# e-Tapperhandpiece14.net
KiCad netlist of a schematic drawn in EAGLE
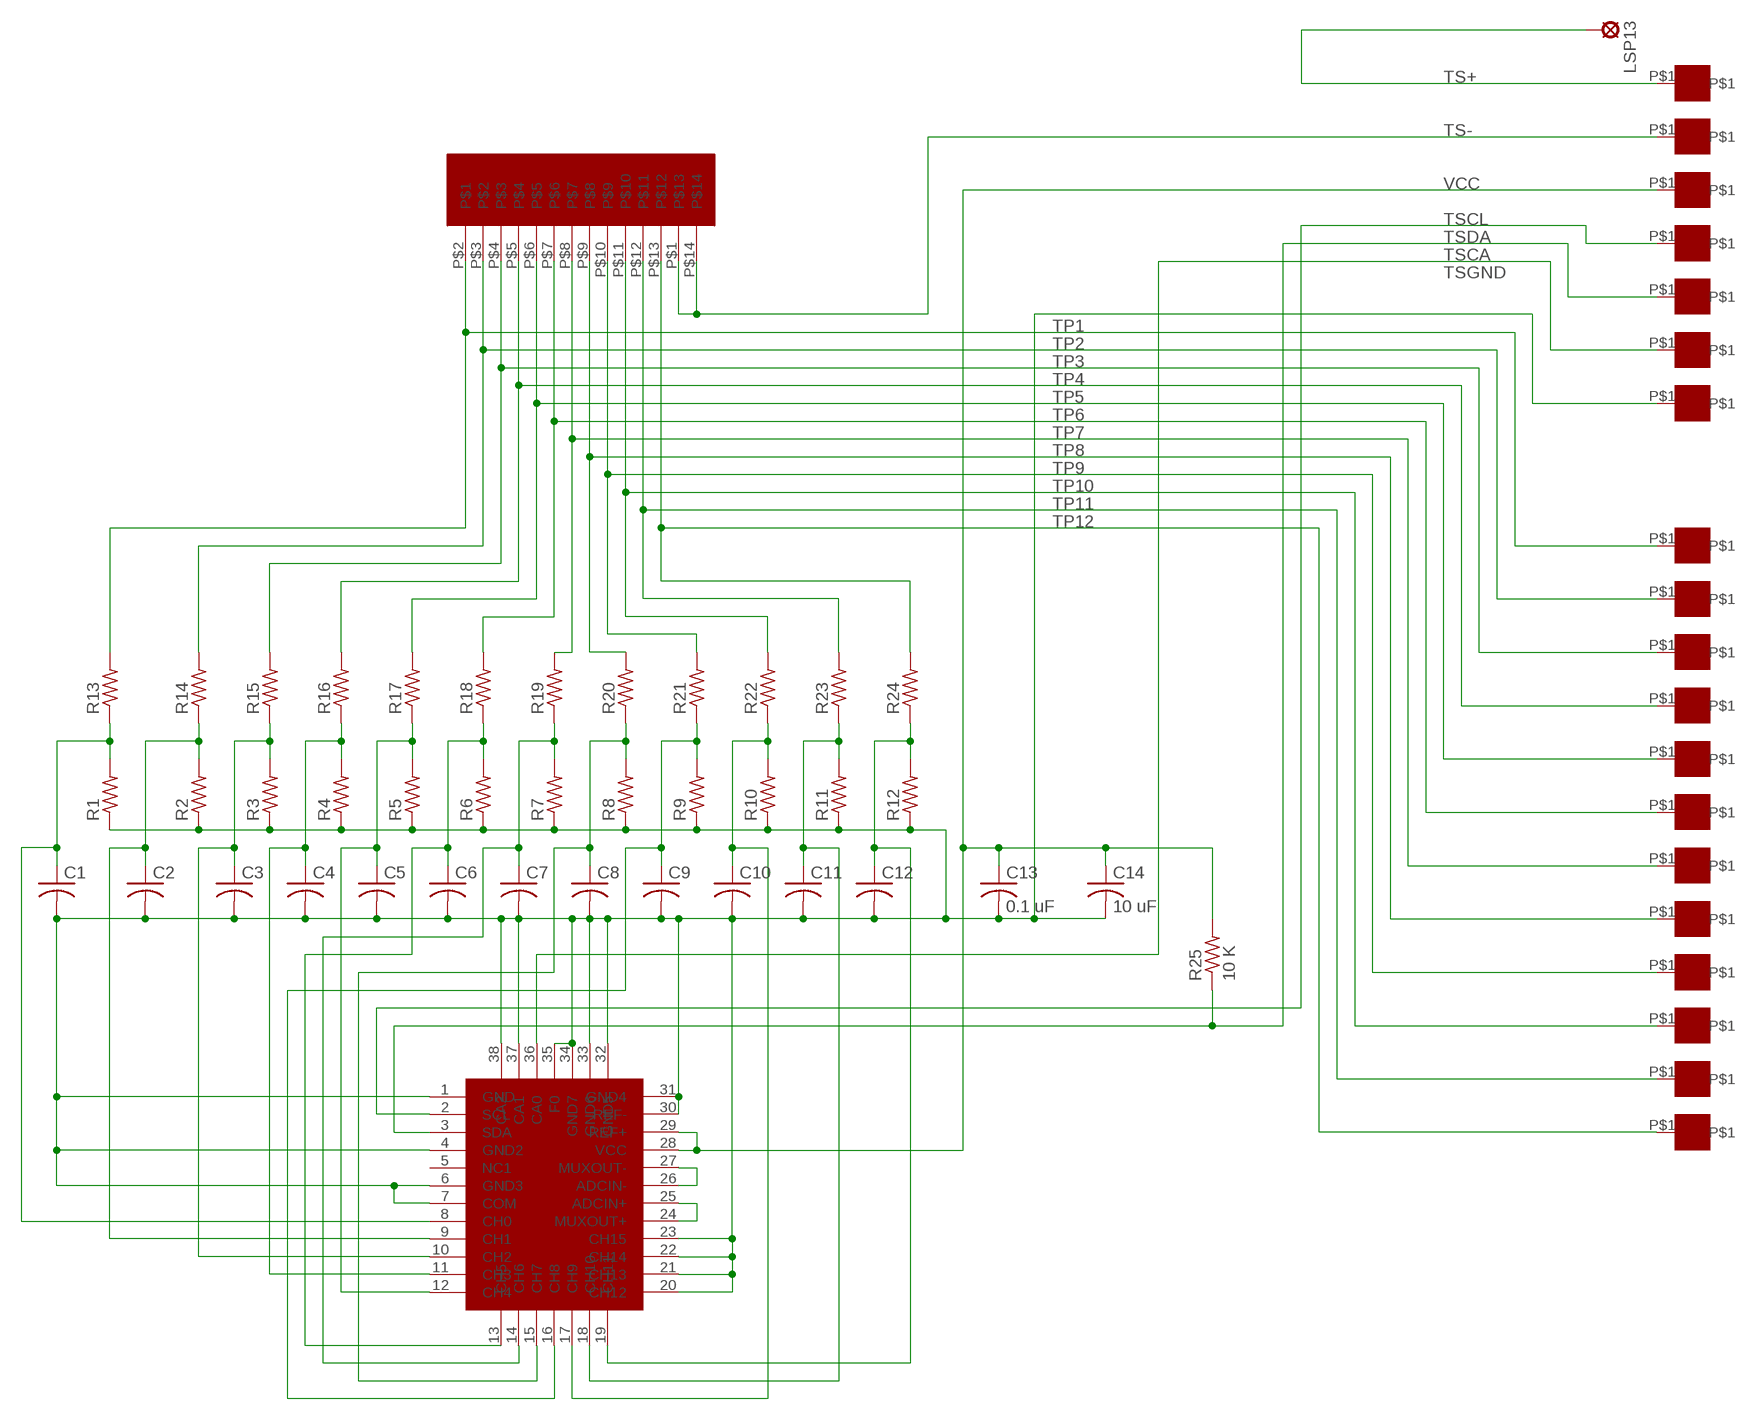
[diagram p0: schematic, sheet 1]

(export (version "E")
  (design (tool "Eeschema 10.0.6"))
  (components
    (comp (ref "C1")
      (value "C-USC0603")
      (footprint "eagle-import:C0603")
      (libsource (lib "eagle-import") (part "C-USC0603"))
    )
    (comp (ref "C2")
      (value "C-USC0603")
      (footprint "eagle-import:C0603")
      (libsource (lib "eagle-import") (part "C-USC0603"))
    )
    (comp (ref "C3")
      (value "C-USC0603")
      (footprint "eagle-import:C0603")
      (libsource (lib "eagle-import") (part "C-USC0603"))
    )
    (comp (ref "C4")
      (value "C-USC0603")
      (footprint "eagle-import:C0603")
      (libsource (lib "eagle-import") (part "C-USC0603"))
    )
    (comp (ref "C5")
      (value "C-USC0603")
      (footprint "eagle-import:C0603")
      (libsource (lib "eagle-import") (part "C-USC0603"))
    )
    (comp (ref "C6")
      (value "C-USC0603")
      (footprint "eagle-import:C0603")
      (libsource (lib "eagle-import") (part "C-USC0603"))
    )
    (comp (ref "C7")
      (value "C-USC0603")
      (footprint "eagle-import:C0603")
      (libsource (lib "eagle-import") (part "C-USC0603"))
    )
    (comp (ref "C8")
      (value "C-USC0603")
      (footprint "eagle-import:C0603")
      (libsource (lib "eagle-import") (part "C-USC0603"))
    )
    (comp (ref "C9")
      (value "C-USC0603")
      (footprint "eagle-import:C0603")
      (libsource (lib "eagle-import") (part "C-USC0603"))
    )
    (comp (ref "C10")
      (value "C-USC0603")
      (footprint "eagle-import:C0603")
      (libsource (lib "eagle-import") (part "C-USC0603"))
    )
    (comp (ref "C11")
      (value "C-USC0603")
      (footprint "eagle-import:C0603")
      (libsource (lib "eagle-import") (part "C-USC0603"))
    )
    (comp (ref "C12")
      (value "C-USC0603")
      (footprint "eagle-import:C0603")
      (libsource (lib "eagle-import") (part "C-USC0603"))
    )
    (comp (ref "C13")
      (value "0.1 uF")
      (footprint "eagle-import:C0603")
      (libsource (lib "eagle-import") (part "C-USC0603"))
    )
    (comp (ref "C14")
      (value "10 uF")
      (footprint "eagle-import:C0805")
      (libsource (lib "eagle-import") (part "C-USC0805"))
    )
    (comp (ref "LSP13")
      (value "SE11")
      (footprint "eagle-import:SE11")
      (libsource (lib "eagle-import") (part "SE11"))
    )
    (comp (ref "R1")
      (value "R-US_R0402")
      (footprint "eagle-import:R0402")
      (libsource (lib "eagle-import") (part "R-US_R0402"))
    )
    (comp (ref "R2")
      (value "R-US_R0402")
      (footprint "eagle-import:R0402")
      (libsource (lib "eagle-import") (part "R-US_R0402"))
    )
    (comp (ref "R3")
      (value "R-US_R0402")
      (footprint "eagle-import:R0402")
      (libsource (lib "eagle-import") (part "R-US_R0402"))
    )
    (comp (ref "R4")
      (value "R-US_R0402")
      (footprint "eagle-import:R0402")
      (libsource (lib "eagle-import") (part "R-US_R0402"))
    )
    (comp (ref "R5")
      (value "R-US_R0402")
      (footprint "eagle-import:R0402")
      (libsource (lib "eagle-import") (part "R-US_R0402"))
    )
    (comp (ref "R6")
      (value "R-US_R0402")
      (footprint "eagle-import:R0402")
      (libsource (lib "eagle-import") (part "R-US_R0402"))
    )
    (comp (ref "R7")
      (value "R-US_R0402")
      (footprint "eagle-import:R0402")
      (libsource (lib "eagle-import") (part "R-US_R0402"))
    )
    (comp (ref "R8")
      (value "R-US_R0402")
      (footprint "eagle-import:R0402")
      (libsource (lib "eagle-import") (part "R-US_R0402"))
    )
    (comp (ref "R9")
      (value "R-US_R0402")
      (footprint "eagle-import:R0402")
      (libsource (lib "eagle-import") (part "R-US_R0402"))
    )
    (comp (ref "R10")
      (value "R-US_R0402")
      (footprint "eagle-import:R0402")
      (libsource (lib "eagle-import") (part "R-US_R0402"))
    )
    (comp (ref "R11")
      (value "R-US_R0402")
      (footprint "eagle-import:R0402")
      (libsource (lib "eagle-import") (part "R-US_R0402"))
    )
    (comp (ref "R12")
      (value "R-US_R0402")
      (footprint "eagle-import:R0402")
      (libsource (lib "eagle-import") (part "R-US_R0402"))
    )
    (comp (ref "R13")
      (value "R-US_R0402")
      (footprint "eagle-import:R0402")
      (libsource (lib "eagle-import") (part "R-US_R0402"))
    )
    (comp (ref "R14")
      (value "R-US_R0402")
      (footprint "eagle-import:R0402")
      (libsource (lib "eagle-import") (part "R-US_R0402"))
    )
    (comp (ref "R15")
      (value "R-US_R0402")
      (footprint "eagle-import:R0402")
      (libsource (lib "eagle-import") (part "R-US_R0402"))
    )
    (comp (ref "R16")
      (value "R-US_R0402")
      (footprint "eagle-import:R0402")
      (libsource (lib "eagle-import") (part "R-US_R0402"))
    )
    (comp (ref "R17")
      (value "R-US_R0402")
      (footprint "eagle-import:R0402")
      (libsource (lib "eagle-import") (part "R-US_R0402"))
    )
    (comp (ref "R18")
      (value "R-US_R0402")
      (footprint "eagle-import:R0402")
      (libsource (lib "eagle-import") (part "R-US_R0402"))
    )
    (comp (ref "R19")
      (value "R-US_R0402")
      (footprint "eagle-import:R0402")
      (libsource (lib "eagle-import") (part "R-US_R0402"))
    )
    (comp (ref "R20")
      (value "R-US_R0402")
      (footprint "eagle-import:R0402")
      (libsource (lib "eagle-import") (part "R-US_R0402"))
    )
    (comp (ref "R21")
      (value "R-US_R0402")
      (footprint "eagle-import:R0402")
      (libsource (lib "eagle-import") (part "R-US_R0402"))
    )
    (comp (ref "R22")
      (value "R-US_R0402")
      (footprint "eagle-import:R0402")
      (libsource (lib "eagle-import") (part "R-US_R0402"))
    )
    (comp (ref "R23")
      (value "R-US_R0402")
      (footprint "eagle-import:R0402")
      (libsource (lib "eagle-import") (part "R-US_R0402"))
    )
    (comp (ref "R24")
      (value "R-US_R0402")
      (footprint "eagle-import:R0402")
      (libsource (lib "eagle-import") (part "R-US_R0402"))
    )
    (comp (ref "R25")
      (value "10 K")
      (footprint "eagle-import:R0402")
      (libsource (lib "eagle-import") (part "R-US_R0402"))
    )
    (comp (ref "TSP1")
      (value "ET1")
      (footprint "eagle-import:ET1")
      (libsource (lib "eagle-import") (part "ET1"))
    )
    (comp (ref "TSP2")
      (value "ET1")
      (footprint "eagle-import:ET1")
      (libsource (lib "eagle-import") (part "ET1"))
    )
    (comp (ref "TSP3")
      (value "ET1")
      (footprint "eagle-import:ET1")
      (libsource (lib "eagle-import") (part "ET1"))
    )
    (comp (ref "TSP4")
      (value "ET1")
      (footprint "eagle-import:ET1")
      (libsource (lib "eagle-import") (part "ET1"))
    )
    (comp (ref "TSP5")
      (value "ET1")
      (footprint "eagle-import:ET1")
      (libsource (lib "eagle-import") (part "ET1"))
    )
    (comp (ref "TSP6")
      (value "ET1")
      (footprint "eagle-import:ET1")
      (libsource (lib "eagle-import") (part "ET1"))
    )
    (comp (ref "TSP7")
      (value "ET1")
      (footprint "eagle-import:ET1")
      (libsource (lib "eagle-import") (part "ET1"))
    )
    (comp (ref "TSP8")
      (value "ET1")
      (footprint "eagle-import:ET1")
      (libsource (lib "eagle-import") (part "ET1"))
    )
    (comp (ref "TSP9")
      (value "ET1")
      (footprint "eagle-import:ET1")
      (libsource (lib "eagle-import") (part "ET1"))
    )
    (comp (ref "TSP10")
      (value "ET1")
      (footprint "eagle-import:ET1")
      (libsource (lib "eagle-import") (part "ET1"))
    )
    (comp (ref "TSP11")
      (value "ET1")
      (footprint "eagle-import:ET1")
      (libsource (lib "eagle-import") (part "ET1"))
    )
    (comp (ref "TSP12")
      (value "ET1")
      (footprint "eagle-import:ET1")
      (libsource (lib "eagle-import") (part "ET1"))
    )
    (comp (ref "TSP13")
      (value "ET1")
      (footprint "eagle-import:ET1")
      (libsource (lib "eagle-import") (part "ET1"))
    )
    (comp (ref "TSP14")
      (value "ET1")
      (footprint "eagle-import:ET1")
      (libsource (lib "eagle-import") (part "ET1"))
    )
    (comp (ref "TSP15")
      (value "ET1")
      (footprint "eagle-import:ET1")
      (libsource (lib "eagle-import") (part "ET1"))
    )
    (comp (ref "TSP16")
      (value "ET1")
      (footprint "eagle-import:ET1")
      (libsource (lib "eagle-import") (part "ET1"))
    )
    (comp (ref "TSP17")
      (value "ET1")
      (footprint "eagle-import:ET1")
      (libsource (lib "eagle-import") (part "ET1"))
    )
    (comp (ref "TSP18")
      (value "ET1")
      (footprint "eagle-import:ET1")
      (libsource (lib "eagle-import") (part "ET1"))
    )
    (comp (ref "TSP19")
      (value "ET1")
      (footprint "eagle-import:ET1")
      (libsource (lib "eagle-import") (part "ET1"))
    )
    (comp (ref "U$1")
      (value "LTC2497")
      (footprint "eagle-import:QFN38-5X7")
      (libsource (lib "eagle-import") (part "LTC2497"))
    )
    (comp (ref "U$2")
      (value "SS112D01")
      (footprint "eagle-import:SS112D01")
      (libsource (lib "eagle-import") (part "SS112D01"))
    )
  )
  (nets
    (net (code "1") (name "/TP1") (class "Default")
      (node (ref "R13") (pin "2") (pinfunction "2_2") (pintype "passive"))
      (node (ref "TSP1") (pin "P$1") (pinfunction "P$1_P$1") (pintype "bidirectional"))
      (node (ref "U$2") (pin "P$2") (pinfunction "P$1_P$2") (pintype "bidirectional"))
    )
    (net (code "2") (name "/TP2") (class "Default")
      (node (ref "R14") (pin "2") (pinfunction "2_2") (pintype "passive"))
      (node (ref "TSP2") (pin "P$1") (pinfunction "P$1_P$1") (pintype "bidirectional"))
      (node (ref "U$2") (pin "P$3") (pinfunction "P$2_P$3") (pintype "bidirectional"))
    )
    (net (code "3") (name "/TP3") (class "Default")
      (node (ref "R15") (pin "2") (pinfunction "2_2") (pintype "passive"))
      (node (ref "TSP3") (pin "P$1") (pinfunction "P$1_P$1") (pintype "bidirectional"))
      (node (ref "U$2") (pin "P$4") (pinfunction "P$3_P$4") (pintype "bidirectional"))
    )
    (net (code "4") (name "/TP4") (class "Default")
      (node (ref "R16") (pin "2") (pinfunction "2_2") (pintype "passive"))
      (node (ref "TSP4") (pin "P$1") (pinfunction "P$1_P$1") (pintype "bidirectional"))
      (node (ref "U$2") (pin "P$5") (pinfunction "P$4_P$5") (pintype "bidirectional"))
    )
    (net (code "5") (name "/TP5") (class "Default")
      (node (ref "R17") (pin "2") (pinfunction "2_2") (pintype "passive"))
      (node (ref "TSP5") (pin "P$1") (pinfunction "P$1_P$1") (pintype "bidirectional"))
      (node (ref "U$2") (pin "P$6") (pinfunction "P$5_P$6") (pintype "bidirectional"))
    )
    (net (code "6") (name "/TP6") (class "Default")
      (node (ref "R18") (pin "2") (pinfunction "2_2") (pintype "passive"))
      (node (ref "TSP6") (pin "P$1") (pinfunction "P$1_P$1") (pintype "bidirectional"))
      (node (ref "U$2") (pin "P$7") (pinfunction "P$6_P$7") (pintype "bidirectional"))
    )
    (net (code "7") (name "/TP7") (class "Default")
      (node (ref "R19") (pin "2") (pinfunction "2_2") (pintype "passive"))
      (node (ref "TSP7") (pin "P$1") (pinfunction "P$1_P$1") (pintype "bidirectional"))
      (node (ref "U$2") (pin "P$8") (pinfunction "P$7_P$8") (pintype "bidirectional"))
    )
    (net (code "8") (name "/TP8") (class "Default")
      (node (ref "R20") (pin "2") (pinfunction "2_2") (pintype "passive"))
      (node (ref "TSP8") (pin "P$1") (pinfunction "P$1_P$1") (pintype "bidirectional"))
      (node (ref "U$2") (pin "P$9") (pinfunction "P$8_P$9") (pintype "bidirectional"))
    )
    (net (code "9") (name "/TP9") (class "Default")
      (node (ref "R21") (pin "2") (pinfunction "2_2") (pintype "passive"))
      (node (ref "TSP9") (pin "P$1") (pinfunction "P$1_P$1") (pintype "bidirectional"))
      (node (ref "U$2") (pin "P$10") (pinfunction "P$9_P$10") (pintype "bidirectional"))
    )
    (net (code "10") (name "/TP10") (class "Default")
      (node (ref "R22") (pin "2") (pinfunction "2_2") (pintype "passive"))
      (node (ref "TSP10") (pin "P$1") (pinfunction "P$1_P$1") (pintype "bidirectional"))
      (node (ref "U$2") (pin "P$11") (pinfunction "P$10_P$11") (pintype "bidirectional"))
    )
    (net (code "11") (name "/TP11") (class "Default")
      (node (ref "R23") (pin "2") (pinfunction "2_2") (pintype "passive"))
      (node (ref "TSP11") (pin "P$1") (pinfunction "P$1_P$1") (pintype "bidirectional"))
      (node (ref "U$2") (pin "P$12") (pinfunction "P$11_P$12") (pintype "bidirectional"))
    )
    (net (code "12") (name "/TP12") (class "Default")
      (node (ref "R24") (pin "2") (pinfunction "2_2") (pintype "passive"))
      (node (ref "TSP12") (pin "P$1") (pinfunction "P$1_P$1") (pintype "bidirectional"))
      (node (ref "U$2") (pin "P$13") (pinfunction "P$12_P$13") (pintype "bidirectional"))
    )
    (net (code "13") (name "/TS+") (class "Default")
      (node (ref "LSP13") (pin "MP") (pinfunction "MP_MP") (pintype "passive"))
      (node (ref "TSP13") (pin "P$1") (pinfunction "P$1_P$1") (pintype "bidirectional"))
    )
    (net (code "14") (name "/TS-") (class "Default")
      (node (ref "TSP14") (pin "P$1") (pinfunction "P$1_P$1") (pintype "bidirectional"))
      (node (ref "U$2") (pin "P$1") (pinfunction "P$13_P$1") (pintype "bidirectional"))
      (node (ref "U$2") (pin "P$14") (pinfunction "P$14_P$14") (pintype "bidirectional"))
    )
    (net (code "15") (name "/TSCA") (class "Default")
      (node (ref "TSP18") (pin "P$1") (pinfunction "P$1_P$1") (pintype "bidirectional"))
      (node (ref "U$1") (pin "36") (pinfunction "CA0_36") (pintype "bidirectional"))
    )
    (net (code "16") (name "/TSCL") (class "Default")
      (node (ref "TSP16") (pin "P$1") (pinfunction "P$1_P$1") (pintype "bidirectional"))
      (node (ref "U$1") (pin "2") (pinfunction "SCL_2") (pintype "bidirectional"))
    )
    (net (code "17") (name "/TSDA") (class "Default")
      (node (ref "R25") (pin "1") (pinfunction "1_1") (pintype "passive"))
      (node (ref "TSP17") (pin "P$1") (pinfunction "P$1_P$1") (pintype "bidirectional"))
      (node (ref "U$1") (pin "3") (pinfunction "SDA_3") (pintype "bidirectional"))
    )
    (net (code "18") (name "/TSGND") (class "Default")
      (node (ref "C1") (pin "2") (pinfunction "2_2") (pintype "passive"))
      (node (ref "C10") (pin "2") (pinfunction "2_2") (pintype "passive"))
      (node (ref "C11") (pin "2") (pinfunction "2_2") (pintype "passive"))
      (node (ref "C12") (pin "2") (pinfunction "2_2") (pintype "passive"))
      (node (ref "C13") (pin "2") (pinfunction "2_2") (pintype "passive"))
      (node (ref "C14") (pin "2") (pinfunction "2_2") (pintype "passive"))
      (node (ref "C2") (pin "2") (pinfunction "2_2") (pintype "passive"))
      (node (ref "C3") (pin "2") (pinfunction "2_2") (pintype "passive"))
      (node (ref "C4") (pin "2") (pinfunction "2_2") (pintype "passive"))
      (node (ref "C5") (pin "2") (pinfunction "2_2") (pintype "passive"))
      (node (ref "C6") (pin "2") (pinfunction "2_2") (pintype "passive"))
      (node (ref "C7") (pin "2") (pinfunction "2_2") (pintype "passive"))
      (node (ref "C8") (pin "2") (pinfunction "2_2") (pintype "passive"))
      (node (ref "C9") (pin "2") (pinfunction "2_2") (pintype "passive"))
      (node (ref "R1") (pin "1") (pinfunction "1_1") (pintype "passive"))
      (node (ref "R10") (pin "1") (pinfunction "1_1") (pintype "passive"))
      (node (ref "R11") (pin "1") (pinfunction "1_1") (pintype "passive"))
      (node (ref "R12") (pin "1") (pinfunction "1_1") (pintype "passive"))
      (node (ref "R2") (pin "1") (pinfunction "1_1") (pintype "passive"))
      (node (ref "R3") (pin "1") (pinfunction "1_1") (pintype "passive"))
      (node (ref "R4") (pin "1") (pinfunction "1_1") (pintype "passive"))
      (node (ref "R5") (pin "1") (pinfunction "1_1") (pintype "passive"))
      (node (ref "R6") (pin "1") (pinfunction "1_1") (pintype "passive"))
      (node (ref "R7") (pin "1") (pinfunction "1_1") (pintype "passive"))
      (node (ref "R8") (pin "1") (pinfunction "1_1") (pintype "passive"))
      (node (ref "R9") (pin "1") (pinfunction "1_1") (pintype "passive"))
      (node (ref "TSP19") (pin "P$1") (pinfunction "P$1_P$1") (pintype "bidirectional"))
      (node (ref "U$1") (pin "1") (pinfunction "GND_1") (pintype "power_in"))
      (node (ref "U$1") (pin "20") (pinfunction "CH12_20") (pintype "input"))
      (node (ref "U$1") (pin "21") (pinfunction "CH13_21") (pintype "input"))
      (node (ref "U$1") (pin "22") (pinfunction "CH14_22") (pintype "input"))
      (node (ref "U$1") (pin "23") (pinfunction "CH15_23") (pintype "input"))
      (node (ref "U$1") (pin "30") (pinfunction "REF-_30") (pintype "bidirectional"))
      (node (ref "U$1") (pin "31") (pinfunction "GND4_31") (pintype "power_in"))
      (node (ref "U$1") (pin "32") (pinfunction "GND5_32") (pintype "power_in"))
      (node (ref "U$1") (pin "33") (pinfunction "GND6_33") (pintype "power_in"))
      (node (ref "U$1") (pin "34") (pinfunction "GND7_34") (pintype "power_in"))
      (node (ref "U$1") (pin "35") (pinfunction "F0_35") (pintype "bidirectional"))
      (node (ref "U$1") (pin "37") (pinfunction "CA1_37") (pintype "bidirectional"))
      (node (ref "U$1") (pin "38") (pinfunction "CA2_38") (pintype "bidirectional"))
      (node (ref "U$1") (pin "4") (pinfunction "GND2_4") (pintype "power_in"))
      (node (ref "U$1") (pin "6") (pinfunction "GND3_6") (pintype "power_in"))
      (node (ref "U$1") (pin "7") (pinfunction "COM_7") (pintype "power_in"))
    )
    (net (code "19") (name "/VCC") (class "Default")
      (node (ref "C13") (pin "1") (pinfunction "1_1") (pintype "passive"))
      (node (ref "C14") (pin "1") (pinfunction "1_1") (pintype "passive"))
      (node (ref "R25") (pin "2") (pinfunction "2_2") (pintype "passive"))
      (node (ref "TSP15") (pin "P$1") (pinfunction "P$1_P$1") (pintype "bidirectional"))
      (node (ref "U$1") (pin "28") (pinfunction "VCC_28") (pintype "power_in"))
      (node (ref "U$1") (pin "29") (pinfunction "REF+_29") (pintype "bidirectional"))
    )
    (net (code "20") (name "Net-(U$1-ADCIN+)") (class "Default")
      (node (ref "U$1") (pin "24") (pinfunction "MUXOUT+_24") (pintype "bidirectional"))
      (node (ref "U$1") (pin "25") (pinfunction "ADCIN+_25") (pintype "bidirectional"))
    )
    (net (code "21") (name "Net-(U$1-ADCIN-)") (class "Default")
      (node (ref "U$1") (pin "26") (pinfunction "ADCIN-_26") (pintype "bidirectional"))
      (node (ref "U$1") (pin "27") (pinfunction "MUXOUT-_27") (pintype "bidirectional"))
    )
    (net (code "22") (name "Net-(U$1-CH0)") (class "Default")
      (node (ref "C1") (pin "1") (pinfunction "1_1") (pintype "passive"))
      (node (ref "R1") (pin "2") (pinfunction "2_2") (pintype "passive"))
      (node (ref "R13") (pin "1") (pinfunction "1_1") (pintype "passive"))
      (node (ref "U$1") (pin "8") (pinfunction "CH0_8") (pintype "input"))
    )
    (net (code "23") (name "Net-(U$1-CH1)") (class "Default")
      (node (ref "C2") (pin "1") (pinfunction "1_1") (pintype "passive"))
      (node (ref "R14") (pin "1") (pinfunction "1_1") (pintype "passive"))
      (node (ref "R2") (pin "2") (pinfunction "2_2") (pintype "passive"))
      (node (ref "U$1") (pin "9") (pinfunction "CH1_9") (pintype "input"))
    )
    (net (code "24") (name "Net-(U$1-CH2)") (class "Default")
      (node (ref "C3") (pin "1") (pinfunction "1_1") (pintype "passive"))
      (node (ref "R15") (pin "1") (pinfunction "1_1") (pintype "passive"))
      (node (ref "R3") (pin "2") (pinfunction "2_2") (pintype "passive"))
      (node (ref "U$1") (pin "10") (pinfunction "CH2_10") (pintype "input"))
    )
    (net (code "25") (name "Net-(U$1-CH3)") (class "Default")
      (node (ref "C4") (pin "1") (pinfunction "1_1") (pintype "passive"))
      (node (ref "R16") (pin "1") (pinfunction "1_1") (pintype "passive"))
      (node (ref "R4") (pin "2") (pinfunction "2_2") (pintype "passive"))
      (node (ref "U$1") (pin "11") (pinfunction "CH3_11") (pintype "input"))
    )
    (net (code "26") (name "Net-(U$1-CH4)") (class "Default")
      (node (ref "C5") (pin "1") (pinfunction "1_1") (pintype "passive"))
      (node (ref "R17") (pin "1") (pinfunction "1_1") (pintype "passive"))
      (node (ref "R5") (pin "2") (pinfunction "2_2") (pintype "passive"))
      (node (ref "U$1") (pin "12") (pinfunction "CH4_12") (pintype "input"))
    )
    (net (code "27") (name "Net-(U$1-CH5)") (class "Default")
      (node (ref "C6") (pin "1") (pinfunction "1_1") (pintype "passive"))
      (node (ref "R18") (pin "1") (pinfunction "1_1") (pintype "passive"))
      (node (ref "R6") (pin "2") (pinfunction "2_2") (pintype "passive"))
      (node (ref "U$1") (pin "13") (pinfunction "CH5_13") (pintype "input"))
    )
    (net (code "28") (name "Net-(U$1-CH6)") (class "Default")
      (node (ref "C7") (pin "1") (pinfunction "1_1") (pintype "passive"))
      (node (ref "R19") (pin "1") (pinfunction "1_1") (pintype "passive"))
      (node (ref "R7") (pin "2") (pinfunction "2_2") (pintype "passive"))
      (node (ref "U$1") (pin "14") (pinfunction "CH6_14") (pintype "input"))
    )
    (net (code "29") (name "Net-(U$1-CH7)") (class "Default")
      (node (ref "C8") (pin "1") (pinfunction "1_1") (pintype "passive"))
      (node (ref "R20") (pin "1") (pinfunction "1_1") (pintype "passive"))
      (node (ref "R8") (pin "2") (pinfunction "2_2") (pintype "passive"))
      (node (ref "U$1") (pin "15") (pinfunction "CH7_15") (pintype "input"))
    )
    (net (code "30") (name "Net-(U$1-CH8)") (class "Default")
      (node (ref "C9") (pin "1") (pinfunction "1_1") (pintype "passive"))
      (node (ref "R21") (pin "1") (pinfunction "1_1") (pintype "passive"))
      (node (ref "R9") (pin "2") (pinfunction "2_2") (pintype "passive"))
      (node (ref "U$1") (pin "16") (pinfunction "CH8_16") (pintype "input"))
    )
    (net (code "31") (name "Net-(U$1-CH9)") (class "Default")
      (node (ref "C10") (pin "1") (pinfunction "1_1") (pintype "passive"))
      (node (ref "R10") (pin "2") (pinfunction "2_2") (pintype "passive"))
      (node (ref "R22") (pin "1") (pinfunction "1_1") (pintype "passive"))
      (node (ref "U$1") (pin "17") (pinfunction "CH9_17") (pintype "input"))
    )
    (net (code "32") (name "Net-(U$1-CH10)") (class "Default")
      (node (ref "C11") (pin "1") (pinfunction "1_1") (pintype "passive"))
      (node (ref "R11") (pin "2") (pinfunction "2_2") (pintype "passive"))
      (node (ref "R23") (pin "1") (pinfunction "1_1") (pintype "passive"))
      (node (ref "U$1") (pin "18") (pinfunction "CH10_18") (pintype "input"))
    )
    (net (code "33") (name "Net-(U$1-CH11)") (class "Default")
      (node (ref "C12") (pin "1") (pinfunction "1_1") (pintype "passive"))
      (node (ref "R12") (pin "2") (pinfunction "2_2") (pintype "passive"))
      (node (ref "R24") (pin "1") (pinfunction "1_1") (pintype "passive"))
      (node (ref "U$1") (pin "19") (pinfunction "CH11_19") (pintype "input"))
    )
    (net (code "34") (name "unconnected-(U$1-NC1-Pad5)") (class "Default")
      (node (ref "U$1") (pin "5") (pinfunction "NC1_5") (pintype "no_connect"))
    )
  )
)
